# HS100B.net
KiCad netlist of a schematic drawn in Altium Designer
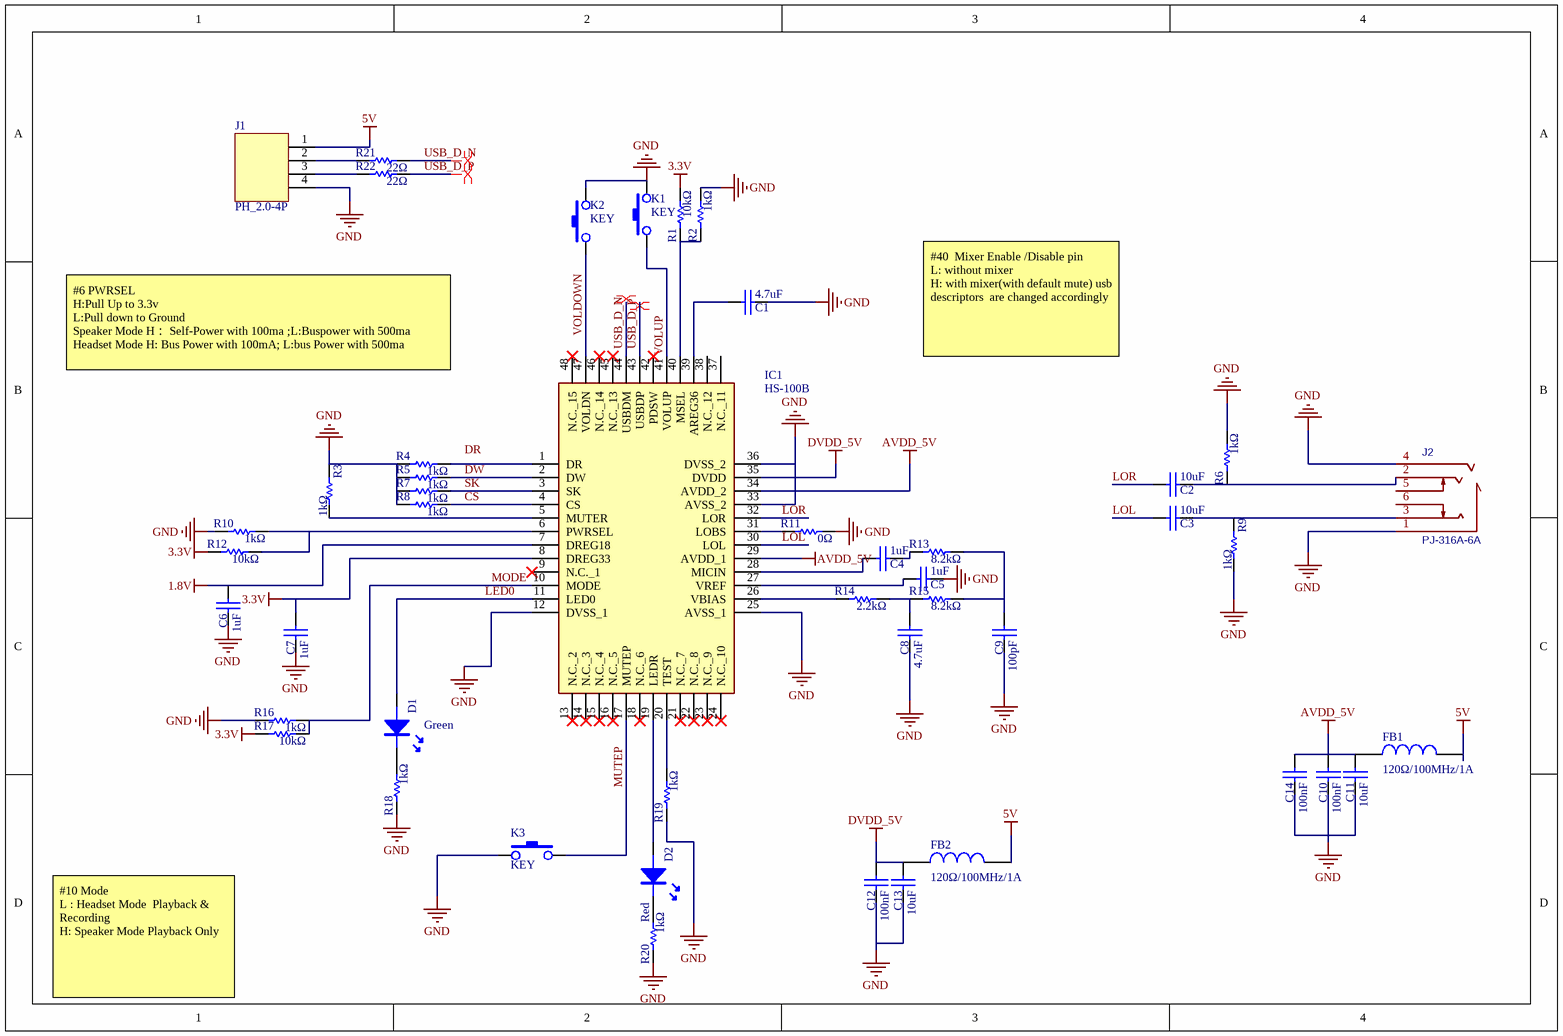
[diagram p0: HS100B.SchDoc]

(export (version "E")
  (design (tool "Eeschema 10.0.6"))
  (components
    (comp (ref "C1")
      (value "4.7uF")
      (footprint "C_0603")
      (description "贴片电容")
      (libsource (lib "IntLib-Passive") (part "Cap_Chip"))
    )
    (comp (ref "C2")
      (value "10uF")
      (footprint "C_0402")
      (description "贴片电容")
      (libsource (lib "IntLib-Passive") (part "Cap_Chip"))
    )
    (comp (ref "C3")
      (value "10uF")
      (footprint "C_0402")
      (description "贴片电容")
      (libsource (lib "IntLib-Passive") (part "Cap_Chip"))
    )
    (comp (ref "C4")
      (value "1uF")
      (footprint "C_0402")
      (description "贴片电容")
      (libsource (lib "IntLib-Passive") (part "Cap_Chip"))
    )
    (comp (ref "C5")
      (value "1uF")
      (footprint "C_0402")
      (description "贴片电容")
      (libsource (lib "IntLib-Passive") (part "Cap_Chip"))
    )
    (comp (ref "C6")
      (value "1uF")
      (footprint "C_0402")
      (description "贴片电容")
      (libsource (lib "IntLib-Passive") (part "Cap_Chip"))
    )
    (comp (ref "C7")
      (value "1uF")
      (footprint "C_0402")
      (description "贴片电容")
      (libsource (lib "IntLib-Passive") (part "Cap_Chip"))
    )
    (comp (ref "C8")
      (value "4.7uF")
      (footprint "C_0402")
      (description "贴片电容")
      (libsource (lib "IntLib-Passive") (part "Cap_Chip"))
    )
    (comp (ref "C9")
      (value "100pF")
      (footprint "C_0402")
      (description "贴片电容")
      (libsource (lib "IntLib-Passive") (part "Cap_Chip"))
    )
    (comp (ref "C10")
      (value "100nF")
      (footprint "C_0402")
      (description "贴片电容")
      (libsource (lib "IntLib-Passive") (part "Cap_Chip"))
    )
    (comp (ref "C11")
      (value "10uF")
      (footprint "C_0603")
      (description "贴片电容")
      (libsource (lib "IntLib-Passive") (part "Cap_Chip"))
    )
    (comp (ref "C12")
      (value "100nF")
      (footprint "C_0402")
      (description "贴片电容")
      (libsource (lib "IntLib-Passive") (part "Cap_Chip"))
    )
    (comp (ref "C13")
      (value "10uF")
      (footprint "C_0603")
      (description "贴片电容")
      (libsource (lib "IntLib-Passive") (part "Cap_Chip"))
    )
    (comp (ref "C14")
      (value "100nF")
      (footprint "C_0402")
      (description "贴片电容")
      (libsource (lib "IntLib-Passive") (part "Cap_Chip"))
    )
    (comp (ref "D1")
      (value "Green")
      (footprint "LED-0603-G")
      (description "贴片LED")
      (libsource (lib "IntLib-Active") (part "LED_Chip"))
    )
    (comp (ref "D2")
      (value "Red")
      (footprint "LED-0603-R")
      (description "贴片LED")
      (libsource (lib "IntLib-Active") (part "LED_Chip"))
    )
    (comp (ref "FB1")
      (value "120Ω/100MHz/1A")
      (footprint "FB_0603")
      (description "磁珠")
      (libsource (lib "IntLib-Passive") (part "Filter_FB"))
    )
    (comp (ref "FB2")
      (value "120Ω/100MHz/1A")
      (footprint "FB_0603")
      (description "磁珠")
      (libsource (lib "IntLib-Passive") (part "Filter_FB"))
    )
    (comp (ref "IC1")
      (value "HS-100B")
      (footprint "SamacSys:QFP50P900X900X160-48N")
      (description "Integrated Circuit")
      (libsource (lib "*") (part "HS-100B"))
    )
    (comp (ref "J1")
      (value "PH_2.0-4P")
      (footprint "PH2.0-4P")
      (libsource (lib "IntLib-Connector") (part "PH_2.0-4P"))
    )
    (comp (ref "J2")
      (value "PJ-316A-6A")
      (footprint "PJ-316A-6A")
      (description "3.5音频链接座子")
      (libsource (lib "IntLib-Connector") (part "Audio_PJ-316A-6A"))
    )
    (comp (ref "K1")
      (value "KEY")
      (footprint "SMD-6X6X5")
      (description "轻触开关")
      (libsource (lib "IntLib-Switch") (part "KEY"))
    )
    (comp (ref "K2")
      (value "KEY")
      (footprint "SMD-6X6X5")
      (description "轻触开关")
      (libsource (lib "IntLib-Switch") (part "KEY"))
    )
    (comp (ref "K3")
      (value "KEY")
      (footprint "SMD-6X6X5")
      (description "轻触开关")
      (libsource (lib "IntLib-Switch") (part "KEY"))
    )
    (comp (ref "R1")
      (value "10kΩ")
      (footprint "R_0402")
      (description "贴片电阻")
      (libsource (lib "IntLib-Passive") (part "Res_Chip"))
    )
    (comp (ref "R2")
      (value "1kΩ")
      (footprint "R_0402")
      (description "贴片电阻")
      (libsource (lib "IntLib-Passive") (part "Res_Chip"))
    )
    (comp (ref "R3")
      (value "1kΩ")
      (footprint "R_0402")
      (description "贴片电阻")
      (libsource (lib "IntLib-Passive") (part "Res_Chip"))
    )
    (comp (ref "R4")
      (value "1kΩ")
      (footprint "R_0402")
      (description "贴片电阻")
      (libsource (lib "IntLib-Passive") (part "Res_Chip"))
    )
    (comp (ref "R5")
      (value "1kΩ")
      (footprint "R_0402")
      (description "贴片电阻")
      (libsource (lib "IntLib-Passive") (part "Res_Chip"))
    )
    (comp (ref "R6")
      (value "1kΩ")
      (footprint "R_0402")
      (description "贴片电阻")
      (libsource (lib "IntLib-Passive") (part "Res_Chip"))
    )
    (comp (ref "R7")
      (value "1kΩ")
      (footprint "R_0402")
      (description "贴片电阻")
      (libsource (lib "IntLib-Passive") (part "Res_Chip"))
    )
    (comp (ref "R8")
      (value "1kΩ")
      (footprint "R_0402")
      (description "贴片电阻")
      (libsource (lib "IntLib-Passive") (part "Res_Chip"))
    )
    (comp (ref "R9")
      (value "1kΩ")
      (footprint "R_0402")
      (description "贴片电阻")
      (libsource (lib "IntLib-Passive") (part "Res_Chip"))
    )
    (comp (ref "R10")
      (value "1kΩ")
      (footprint "R_0402")
      (description "贴片电阻")
      (libsource (lib "IntLib-Passive") (part "Res_Chip"))
    )
    (comp (ref "R11")
      (value "0Ω")
      (footprint "R_0402")
      (description "贴片电阻")
      (libsource (lib "IntLib-Passive") (part "Res_Chip"))
    )
    (comp (ref "R12")
      (value "10kΩ")
      (footprint "R_0402")
      (description "贴片电阻")
      (libsource (lib "IntLib-Passive") (part "Res_Chip"))
    )
    (comp (ref "R13")
      (value "8.2kΩ")
      (footprint "R_0402")
      (description "贴片电阻")
      (libsource (lib "IntLib-Passive") (part "Res_Chip"))
    )
    (comp (ref "R14")
      (value "2.2kΩ")
      (footprint "R_0402")
      (description "贴片电阻")
      (libsource (lib "IntLib-Passive") (part "Res_Chip"))
    )
    (comp (ref "R15")
      (value "8.2kΩ")
      (footprint "R_0402")
      (description "贴片电阻")
      (libsource (lib "IntLib-Passive") (part "Res_Chip"))
    )
    (comp (ref "R16")
      (value "1kΩ")
      (footprint "R_0402")
      (description "贴片电阻")
      (libsource (lib "IntLib-Passive") (part "Res_Chip"))
    )
    (comp (ref "R17")
      (value "10kΩ")
      (footprint "R_0402")
      (description "贴片电阻")
      (libsource (lib "IntLib-Passive") (part "Res_Chip"))
    )
    (comp (ref "R18")
      (value "1kΩ")
      (footprint "R_0402")
      (description "贴片电阻")
      (libsource (lib "IntLib-Passive") (part "Res_Chip"))
    )
    (comp (ref "R19")
      (value "1kΩ")
      (footprint "R_0402")
      (description "贴片电阻")
      (libsource (lib "IntLib-Passive") (part "Res_Chip"))
    )
    (comp (ref "R20")
      (value "1kΩ")
      (footprint "R_0402")
      (description "贴片电阻")
      (libsource (lib "IntLib-Passive") (part "Res_Chip"))
    )
    (comp (ref "R21")
      (value "22Ω")
      (footprint "R_0402")
      (description "贴片电阻")
      (libsource (lib "IntLib-Passive") (part "Res_Chip"))
    )
    (comp (ref "R22")
      (value "22Ω")
      (footprint "R_0402")
      (description "贴片电阻")
      (libsource (lib "IntLib-Passive") (part "Res_Chip"))
    )
  )
  (nets
    (net (code "1") (name "/CS") (class "Default")
      (node (ref "IC1") (pin "4") (pinfunction "CS_4") (pintype "passive"))
      (node (ref "R8") (pin "2") (pinfunction "2_2") (pintype "passive"))
    )
    (net (code "3") (name "/DW") (class "Default")
      (node (ref "IC1") (pin "2") (pinfunction "DW_2") (pintype "passive"))
      (node (ref "R5") (pin "2") (pinfunction "2_2") (pintype "passive"))
    )
    (net (code "4") (name "/LED0") (class "Default")
      (node (ref "D1") (pin "A") (pinfunction "A_A") (pintype "passive"))
      (node (ref "IC1") (pin "11") (pinfunction "LED0_11") (pintype "passive"))
    )
    (net (code "5") (name "/LOL") (class "Default")
      (node (ref "C3") (pin "1") (pinfunction "1_1") (pintype "passive"))
      (node (ref "IC1") (pin "30") (pinfunction "LOL_30") (pintype "passive"))
    )
    (net (code "6") (name "/LOR") (class "Default")
      (node (ref "C2") (pin "1") (pinfunction "1_1") (pintype "passive"))
      (node (ref "IC1") (pin "32") (pinfunction "LOR_32") (pintype "passive"))
    )
    (net (code "7") (name "/MODE") (class "Default")
      (node (ref "IC1") (pin "10") (pinfunction "MODE_10") (pintype "passive"))
      (node (ref "R16") (pin "2") (pinfunction "2_2") (pintype "passive"))
      (node (ref "R17") (pin "2") (pinfunction "2_2") (pintype "passive"))
    )
    (net (code "8") (name "/MUTEP") (class "Default")
      (node (ref "IC1") (pin "17") (pinfunction "MUTEP_17") (pintype "passive"))
      (node (ref "K3") (pin "3") (pinfunction "3_3") (pintype "passive"))
    )
    (net (code "9") (name "/SK") (class "Default")
      (node (ref "IC1") (pin "3") (pinfunction "SK_3") (pintype "passive"))
      (node (ref "R7") (pin "2") (pinfunction "2_2") (pintype "passive"))
    )
    (net (code "10") (name "/USB_D_N") (class "Default")
      (node (ref "IC1") (pin "44") (pinfunction "USBDM_44") (pintype "passive"))
      (node (ref "R21") (pin "2") (pinfunction "2_2") (pintype "passive"))
    )
    (net (code "11") (name "/USB_D_P") (class "Default")
      (node (ref "IC1") (pin "43") (pinfunction "USBDP_43") (pintype "passive"))
      (node (ref "R22") (pin "2") (pinfunction "2_2") (pintype "passive"))
    )
    (net (code "12") (name "/VOLDOWN") (class "Default")
      (node (ref "IC1") (pin "47") (pinfunction "VOLDN_47") (pintype "passive"))
      (node (ref "K2") (pin "1") (pinfunction "1_1") (pintype "passive"))
    )
    (net (code "13") (name "/VOLUP") (class "Default")
      (node (ref "IC1") (pin "41") (pinfunction "VOLUP_41") (pintype "passive"))
      (node (ref "K1") (pin "1") (pinfunction "1_1") (pintype "passive"))
    )
    (net (code "14") (name "1.8V") (class "Default")
      (node (ref "C6") (pin "1") (pinfunction "1_1") (pintype "passive"))
      (node (ref "IC1") (pin "7") (pinfunction "DREG18_7") (pintype "passive"))
    )
    (net (code "15") (name "3.3V") (class "Default")
      (node (ref "C7") (pin "1") (pinfunction "1_1") (pintype "passive"))
      (node (ref "IC1") (pin "8") (pinfunction "DREG33_8") (pintype "passive"))
      (node (ref "R1") (pin "2") (pinfunction "2_2") (pintype "passive"))
      (node (ref "R12") (pin "1") (pinfunction "1_1") (pintype "passive"))
      (node (ref "R17") (pin "1") (pinfunction "1_1") (pintype "passive"))
    )
    (net (code "16") (name "5V") (class "Default")
      (node (ref "FB1") (pin "2") (pinfunction "2_2") (pintype "passive"))
      (node (ref "FB2") (pin "2") (pinfunction "2_2") (pintype "passive"))
      (node (ref "J1") (pin "1") (pinfunction "1_1") (pintype "passive"))
    )
    (net (code "17") (name "AVDD_5V") (class "Default")
      (node (ref "C10") (pin "1") (pinfunction "1_1") (pintype "passive"))
      (node (ref "C11") (pin "1") (pinfunction "1_1") (pintype "passive"))
      (node (ref "C14") (pin "1") (pinfunction "1_1") (pintype "passive"))
      (node (ref "FB1") (pin "1") (pinfunction "1_1") (pintype "passive"))
      (node (ref "IC1") (pin "29") (pinfunction "AVDD_1_29") (pintype "passive"))
      (node (ref "IC1") (pin "34") (pinfunction "AVDD_2_34") (pintype "passive"))
    )
    (net (code "18") (name "DVDD_5V") (class "Default")
      (node (ref "C12") (pin "1") (pinfunction "1_1") (pintype "passive"))
      (node (ref "C13") (pin "1") (pinfunction "1_1") (pintype "passive"))
      (node (ref "FB2") (pin "1") (pinfunction "1_1") (pintype "passive"))
      (node (ref "IC1") (pin "35") (pinfunction "DVDD_35") (pintype "passive"))
    )
    (net (code "19") (name "GND") (class "Default")
      (node (ref "C1") (pin "2") (pinfunction "2_2") (pintype "passive"))
      (node (ref "C10") (pin "2") (pinfunction "2_2") (pintype "passive"))
      (node (ref "C11") (pin "2") (pinfunction "2_2") (pintype "passive"))
      (node (ref "C12") (pin "2") (pinfunction "2_2") (pintype "passive"))
      (node (ref "C13") (pin "2") (pinfunction "2_2") (pintype "passive"))
      (node (ref "C14") (pin "2") (pinfunction "2_2") (pintype "passive"))
      (node (ref "C5") (pin "2") (pinfunction "2_2") (pintype "passive"))
      (node (ref "C6") (pin "2") (pinfunction "2_2") (pintype "passive"))
      (node (ref "C7") (pin "2") (pinfunction "2_2") (pintype "passive"))
      (node (ref "C8") (pin "2") (pinfunction "2_2") (pintype "passive"))
      (node (ref "C9") (pin "2") (pinfunction "2_2") (pintype "passive"))
      (node (ref "IC1") (pin "12") (pinfunction "DVSS_1_12") (pintype "passive"))
      (node (ref "IC1") (pin "25") (pinfunction "AVSS_1_25") (pintype "passive"))
      (node (ref "IC1") (pin "33") (pinfunction "AVSS_2_33") (pintype "passive"))
      (node (ref "IC1") (pin "36") (pinfunction "DVSS_2_36") (pintype "passive"))
      (node (ref "J1") (pin "4") (pinfunction "4_4") (pintype "passive"))
      (node (ref "J2") (pin "1") (pinfunction "1_1") (pintype "passive"))
      (node (ref "J2") (pin "4") (pinfunction "4_4") (pintype "passive"))
      (node (ref "K1") (pin "3") (pinfunction "3_3") (pintype "passive"))
      (node (ref "K2") (pin "3") (pinfunction "3_3") (pintype "passive"))
      (node (ref "K3") (pin "1") (pinfunction "1_1") (pintype "passive"))
      (node (ref "R10") (pin "1") (pinfunction "1_1") (pintype "passive"))
      (node (ref "R11") (pin "2") (pinfunction "2_2") (pintype "passive"))
      (node (ref "R16") (pin "1") (pinfunction "1_1") (pintype "passive"))
      (node (ref "R18") (pin "1") (pinfunction "1_1") (pintype "passive"))
      (node (ref "R19") (pin "1") (pinfunction "1_1") (pintype "passive"))
      (node (ref "R2") (pin "2") (pinfunction "2_2") (pintype "passive"))
      (node (ref "R20") (pin "1") (pinfunction "1_1") (pintype "passive"))
      (node (ref "R3") (pin "1") (pinfunction "1_1") (pintype "passive"))
      (node (ref "R4") (pin "1") (pinfunction "1_1") (pintype "passive"))
      (node (ref "R5") (pin "1") (pinfunction "1_1") (pintype "passive"))
      (node (ref "R6") (pin "2") (pinfunction "2_2") (pintype "passive"))
      (node (ref "R7") (pin "1") (pinfunction "1_1") (pintype "passive"))
      (node (ref "R8") (pin "1") (pinfunction "1_1") (pintype "passive"))
      (node (ref "R9") (pin "2") (pinfunction "2_2") (pintype "passive"))
    )
    (net (code "20") (name "Net-(C2-Pad2)") (class "Default")
      (node (ref "C2") (pin "2") (pinfunction "2_2") (pintype "passive"))
      (node (ref "J2") (pin "2") (pinfunction "2_2") (pintype "passive"))
      (node (ref "R6") (pin "1") (pinfunction "1_1") (pintype "passive"))
    )
    (net (code "21") (name "Net-(C3-Pad2)") (class "Default")
      (node (ref "C3") (pin "2") (pinfunction "2_2") (pintype "passive"))
      (node (ref "J2") (pin "3") (pinfunction "3_3") (pintype "passive"))
      (node (ref "R9") (pin "1") (pinfunction "1_1") (pintype "passive"))
    )
    (net (code "22") (name "Net-(C4-Pad2)") (class "Default")
      (node (ref "C4") (pin "2") (pinfunction "2_2") (pintype "passive"))
      (node (ref "R13") (pin "1") (pinfunction "1_1") (pintype "passive"))
    )
    (net (code "23") (name "Net-(C8-Pad1)") (class "Default")
      (node (ref "C8") (pin "1") (pinfunction "1_1") (pintype "passive"))
      (node (ref "R14") (pin "2") (pinfunction "2_2") (pintype "passive"))
      (node (ref "R15") (pin "1") (pinfunction "1_1") (pintype "passive"))
    )
    (net (code "24") (name "Net-(C9-Pad1)") (class "Default")
      (node (ref "C9") (pin "1") (pinfunction "1_1") (pintype "passive"))
      (node (ref "R13") (pin "2") (pinfunction "2_2") (pintype "passive"))
      (node (ref "R15") (pin "2") (pinfunction "2_2") (pintype "passive"))
    )
    (net (code "25") (name "Net-(D1-PadK)") (class "Default")
      (node (ref "D1") (pin "K") (pinfunction "K_K") (pintype "passive"))
      (node (ref "R18") (pin "2") (pinfunction "2_2") (pintype "passive"))
    )
    (net (code "26") (name "Net-(D2-PadK)") (class "Default")
      (node (ref "D2") (pin "K") (pinfunction "K_K") (pintype "passive"))
      (node (ref "R20") (pin "2") (pinfunction "2_2") (pintype "passive"))
    )
    (net (code "27") (name "Net-(IC1-AREG36)") (class "Default")
      (node (ref "C1") (pin "1") (pinfunction "1_1") (pintype "passive"))
      (node (ref "IC1") (pin "39") (pinfunction "AREG36_39") (pintype "passive"))
    )
    (net (code "28") (name "Net-(IC1-DR)") (class "Default")
      (node (ref "IC1") (pin "1") (pinfunction "DR_1") (pintype "passive"))
      (node (ref "R4") (pin "2") (pinfunction "2_2") (pintype "passive"))
    )
    (net (code "29") (name "Net-(IC1-LEDR)") (class "Default")
      (node (ref "D2") (pin "A") (pinfunction "A_A") (pintype "passive"))
      (node (ref "IC1") (pin "19") (pinfunction "LEDR_19") (pintype "passive"))
    )
    (net (code "30") (name "Net-(IC1-LOBS)") (class "Default")
      (node (ref "IC1") (pin "31") (pinfunction "LOBS_31") (pintype "passive"))
      (node (ref "R11") (pin "1") (pinfunction "1_1") (pintype "passive"))
    )
    (net (code "31") (name "Net-(IC1-MICIN)") (class "Default")
      (node (ref "C4") (pin "1") (pinfunction "1_1") (pintype "passive"))
      (node (ref "IC1") (pin "28") (pinfunction "MICIN_28") (pintype "passive"))
    )
    (net (code "32") (name "Net-(IC1-MSEL)") (class "Default")
      (node (ref "IC1") (pin "40") (pinfunction "MSEL_40") (pintype "passive"))
      (node (ref "R1") (pin "1") (pinfunction "1_1") (pintype "passive"))
      (node (ref "R2") (pin "1") (pinfunction "1_1") (pintype "passive"))
    )
    (net (code "33") (name "Net-(IC1-MUTER)") (class "Default")
      (node (ref "IC1") (pin "5") (pinfunction "MUTER_5") (pintype "passive"))
      (node (ref "R3") (pin "2") (pinfunction "2_2") (pintype "passive"))
    )
    (net (code "34") (name "Net-(IC1-PWRSEL)") (class "Default")
      (node (ref "IC1") (pin "6") (pinfunction "PWRSEL_6") (pintype "passive"))
      (node (ref "R10") (pin "2") (pinfunction "2_2") (pintype "passive"))
      (node (ref "R12") (pin "2") (pinfunction "2_2") (pintype "passive"))
    )
    (net (code "35") (name "Net-(IC1-TEST)") (class "Default")
      (node (ref "IC1") (pin "20") (pinfunction "TEST_20") (pintype "passive"))
      (node (ref "R19") (pin "2") (pinfunction "2_2") (pintype "passive"))
    )
    (net (code "36") (name "Net-(IC1-VBIAS)") (class "Default")
      (node (ref "IC1") (pin "26") (pinfunction "VBIAS_26") (pintype "passive"))
      (node (ref "R14") (pin "1") (pinfunction "1_1") (pintype "passive"))
    )
    (net (code "37") (name "Net-(IC1-VREF)") (class "Default")
      (node (ref "C5") (pin "1") (pinfunction "1_1") (pintype "passive"))
      (node (ref "IC1") (pin "27") (pinfunction "VREF_27") (pintype "passive"))
    )
    (net (code "38") (name "Net-(J1-Pad2)") (class "Default")
      (node (ref "J1") (pin "2") (pinfunction "2_2") (pintype "passive"))
      (node (ref "R21") (pin "1") (pinfunction "1_1") (pintype "passive"))
    )
    (net (code "39") (name "Net-(J1-Pad3)") (class "Default")
      (node (ref "J1") (pin "3") (pinfunction "3_3") (pintype "passive"))
      (node (ref "R22") (pin "1") (pinfunction "1_1") (pintype "passive"))
    )
    (net (code "40") (name "unconnected-(IC1-N.C._1-Pad9)") (class "Default")
      (node (ref "IC1") (pin "9") (pinfunction "N.C._1_9") (pintype "passive+no_connect"))
    )
    (net (code "41") (name "unconnected-(IC1-N.C._2-Pad13)") (class "Default")
      (node (ref "IC1") (pin "13") (pinfunction "N.C._2_13") (pintype "passive+no_connect"))
    )
    (net (code "42") (name "unconnected-(IC1-N.C._3-Pad14)") (class "Default")
      (node (ref "IC1") (pin "14") (pinfunction "N.C._3_14") (pintype "passive+no_connect"))
    )
    (net (code "43") (name "unconnected-(IC1-N.C._4-Pad15)") (class "Default")
      (node (ref "IC1") (pin "15") (pinfunction "N.C._4_15") (pintype "passive+no_connect"))
    )
    (net (code "44") (name "unconnected-(IC1-N.C._5-Pad16)") (class "Default")
      (node (ref "IC1") (pin "16") (pinfunction "N.C._5_16") (pintype "passive+no_connect"))
    )
    (net (code "45") (name "unconnected-(IC1-N.C._6-Pad18)") (class "Default")
      (node (ref "IC1") (pin "18") (pinfunction "N.C._6_18") (pintype "passive+no_connect"))
    )
    (net (code "46") (name "unconnected-(IC1-N.C._7-Pad21)") (class "Default")
      (node (ref "IC1") (pin "21") (pinfunction "N.C._7_21") (pintype "passive+no_connect"))
    )
    (net (code "47") (name "unconnected-(IC1-N.C._8-Pad22)") (class "Default")
      (node (ref "IC1") (pin "22") (pinfunction "N.C._8_22") (pintype "passive+no_connect"))
    )
    (net (code "48") (name "unconnected-(IC1-N.C._9-Pad23)") (class "Default")
      (node (ref "IC1") (pin "23") (pinfunction "N.C._9_23") (pintype "passive+no_connect"))
    )
    (net (code "49") (name "unconnected-(IC1-N.C._10-Pad24)") (class "Default")
      (node (ref "IC1") (pin "24") (pinfunction "N.C._10_24") (pintype "passive+no_connect"))
    )
    (net (code "50") (name "unconnected-(IC1-N.C._11-Pad37)") (class "Default")
      (node (ref "IC1") (pin "37") (pinfunction "N.C._11_37") (pintype "passive"))
    )
    (net (code "51") (name "unconnected-(IC1-N.C._12-Pad38)") (class "Default")
      (node (ref "IC1") (pin "38") (pinfunction "N.C._12_38") (pintype "passive"))
    )
    (net (code "52") (name "unconnected-(IC1-N.C._13-Pad45)") (class "Default")
      (node (ref "IC1") (pin "45") (pinfunction "N.C._13_45") (pintype "passive+no_connect"))
    )
    (net (code "53") (name "unconnected-(IC1-N.C._14-Pad46)") (class "Default")
      (node (ref "IC1") (pin "46") (pinfunction "N.C._14_46") (pintype "passive+no_connect"))
    )
    (net (code "54") (name "unconnected-(IC1-N.C._15-Pad48)") (class "Default")
      (node (ref "IC1") (pin "48") (pinfunction "N.C._15_48") (pintype "passive+no_connect"))
    )
    (net (code "55") (name "unconnected-(IC1-PDSW-Pad42)") (class "Default")
      (node (ref "IC1") (pin "42") (pinfunction "PDSW_42") (pintype "passive+no_connect"))
    )
    (net (code "56") (name "unconnected-(J2-Pad5)") (class "Default")
      (node (ref "J2") (pin "5") (pinfunction "5_5") (pintype "passive"))
    )
    (net (code "57") (name "unconnected-(J2-Pad6)") (class "Default")
      (node (ref "J2") (pin "6") (pinfunction "6_6") (pintype "passive"))
    )
  )
)
